# VOLTAGE_TOP.net
KiCad netlist of a schematic drawn in Altium Designer
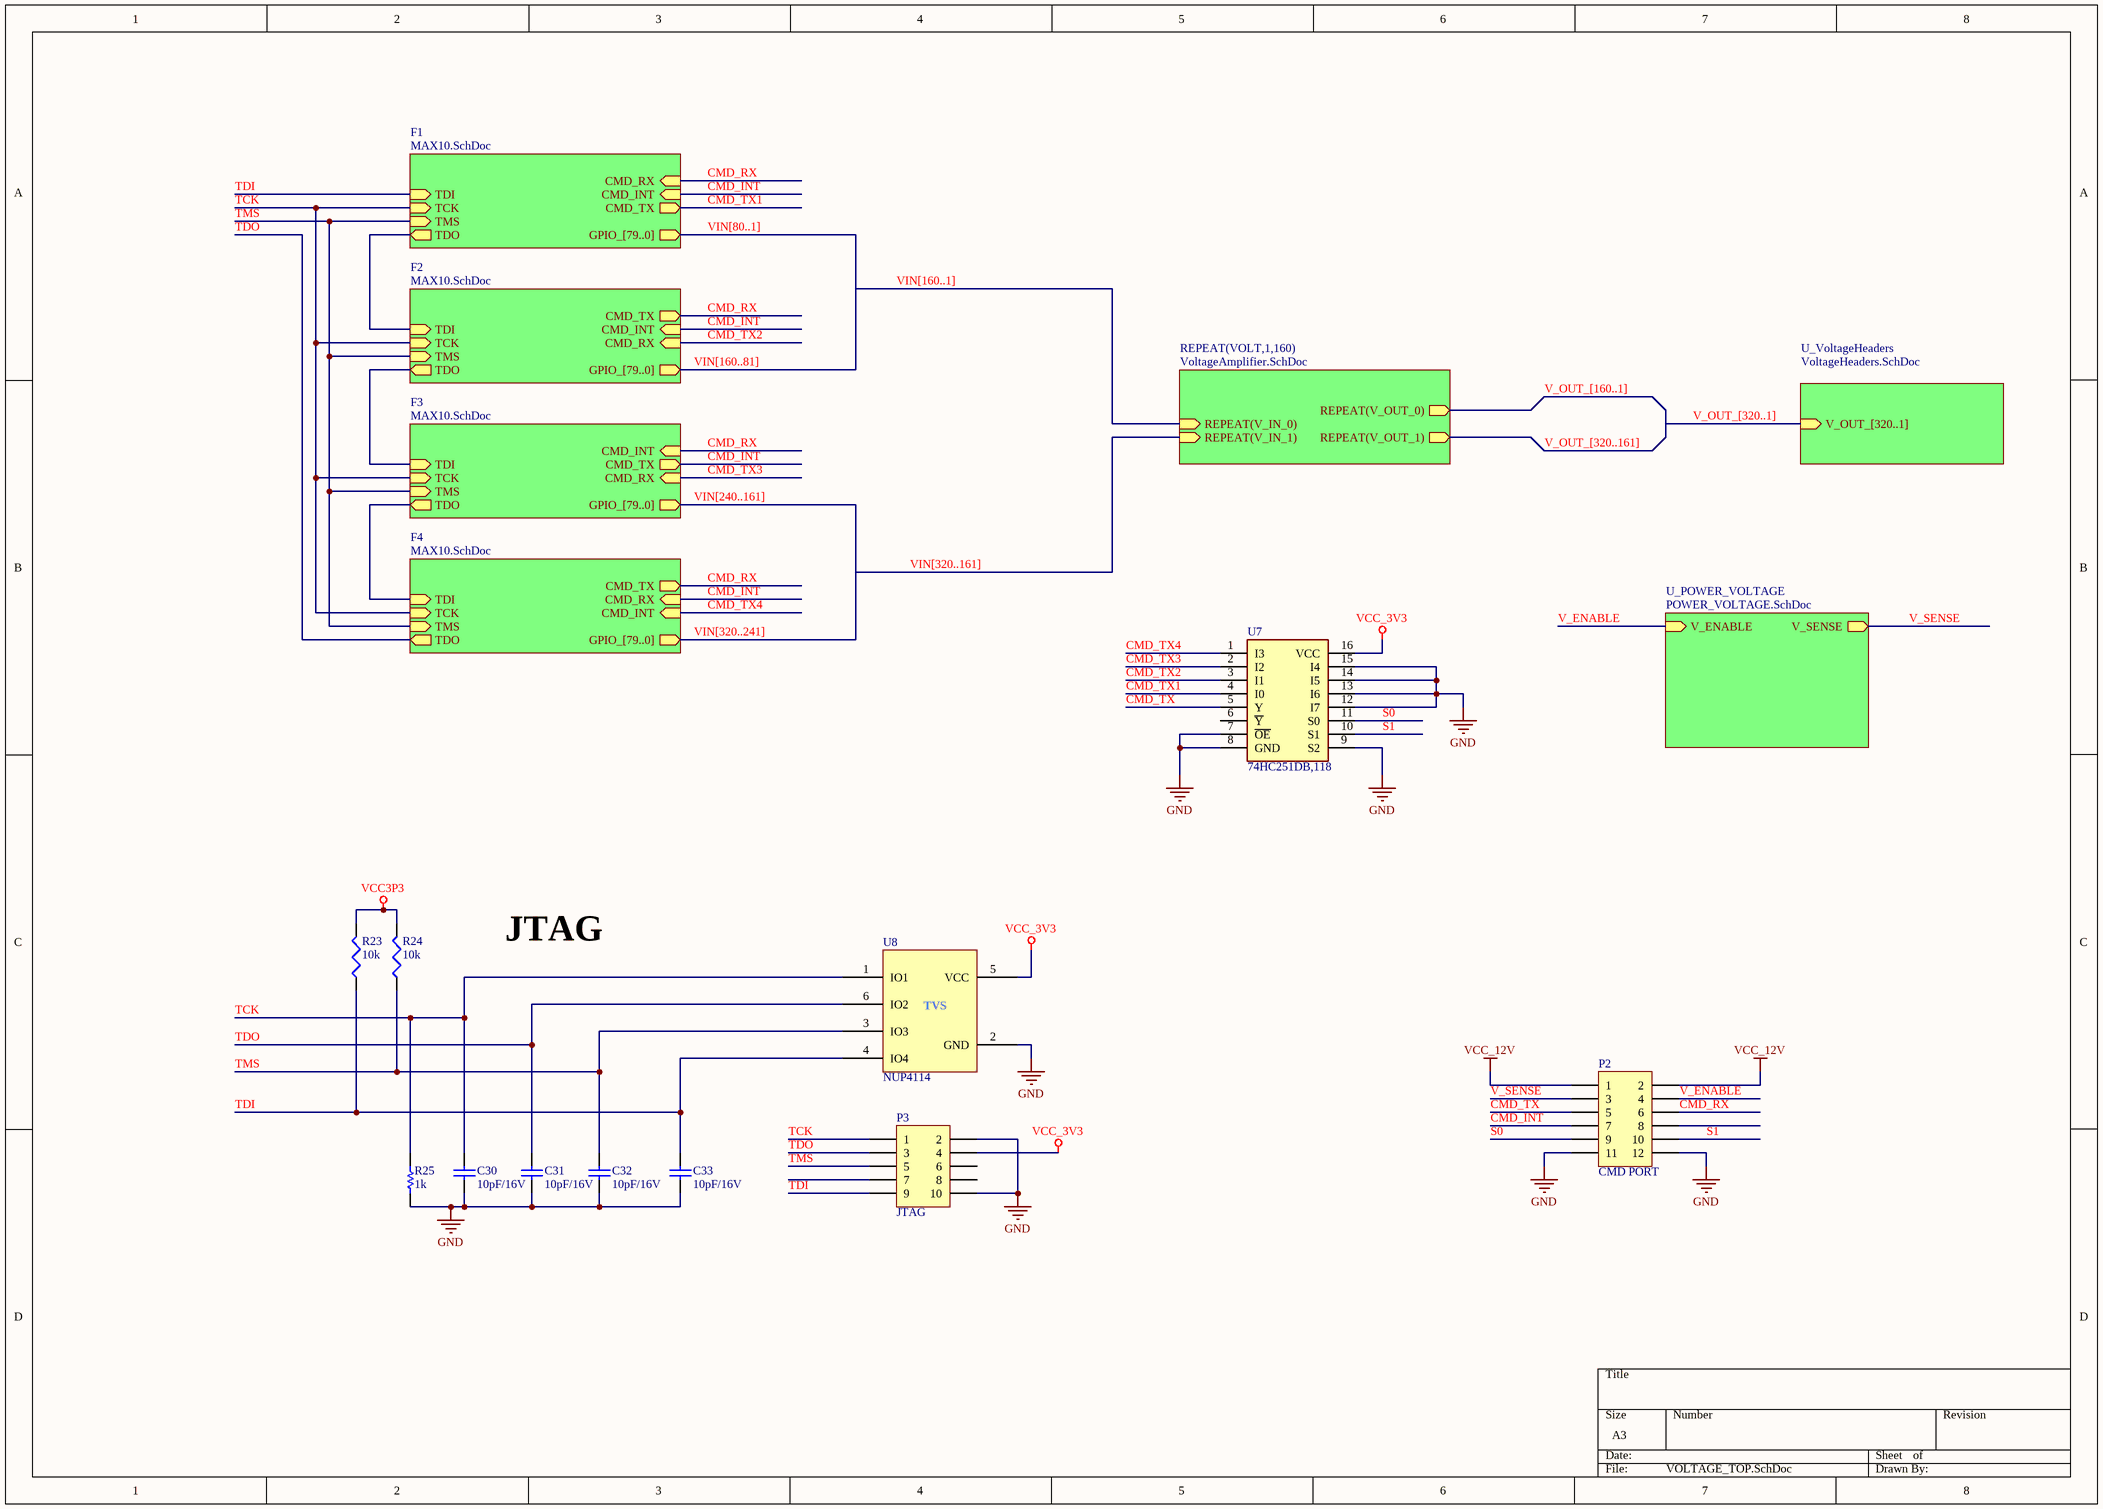
[diagram p0: VOLTAGE_TOP.SchDoc]

(export (version "E")
  (design (tool "Eeschema 10.0.6"))
  (components
    (comp (ref "C30")
      (value "10pF/16V")
      (footprint "0603_CAP")
      (description "Multilayer Ceramic Capacitors MLCC - SMD/SMT 16V 10pF 0603 X7R 0.1")
      (fields
        (field (name "STOCKIEST PART NO") "80-C0603C100K4RACTU")
        (field (name "MFR PART NO") "C0603C100K4RACTU")
      )
      (libsource (lib "Miscellaneous Devices") (part "Cap"))
    )
    (comp (ref "C31")
      (value "10pF/16V")
      (footprint "0603_CAP")
      (description "Multilayer Ceramic Capacitors MLCC - SMD/SMT 16V 10pF 0603 X7R 0.1")
      (fields
        (field (name "STOCKIEST PART NO") "80-C0603C100K4RACTU")
        (field (name "MFR PART NO") "C0603C100K4RACTU")
      )
      (libsource (lib "Miscellaneous Devices") (part "Cap"))
    )
    (comp (ref "C32")
      (value "10pF/16V")
      (footprint "0603_CAP")
      (description "Multilayer Ceramic Capacitors MLCC - SMD/SMT 16V 10pF 0603 X7R 0.1")
      (fields
        (field (name "STOCKIEST PART NO") "80-C0603C100K4RACTU")
        (field (name "MFR PART NO") "C0603C100K4RACTU")
      )
      (libsource (lib "Miscellaneous Devices") (part "Cap"))
    )
    (comp (ref "C33")
      (value "10pF/16V")
      (footprint "0603_CAP")
      (description "Multilayer Ceramic Capacitors MLCC - SMD/SMT 16V 10pF 0603 X7R 0.1")
      (fields
        (field (name "STOCKIEST PART NO") "80-C0603C100K4RACTU")
        (field (name "MFR PART NO") "C0603C100K4RACTU")
      )
      (libsource (lib "Miscellaneous Devices") (part "Cap"))
    )
    (comp (ref "P2")
      (value "CMD PORT")
      (footprint "HDR2X6")
      (description "Header, 6-Pin, Dual row")
      (fields (field (name "PUBLISHER") "Altium Limited"))
      (libsource (lib "Miscellaneous Connectors") (part "Header 6X2"))
    )
    (comp (ref "P3")
      (value "JTAG")
      (footprint "HDR2X5")
      (description "Header, 5-Pin, Dual row")
      (fields (field (name "PUBLISHER") "Altium Limited"))
      (libsource (lib "Miscellaneous Connectors") (part "Header 5X2"))
    )
    (comp (ref "R23")
      (value "10k")
      (footprint "0402_RES")
      (description "Thick Film Resistors - SMD 10K OHM 1%")
      (fields (field (name "MANUFACTURER") "Yageo") (field (name "STOCKIEST PART NO") "603-RC0402FR-0710KL"))
      (libsource (lib "altium-import") (part "root_1_0402_RES_"))
    )
    (comp (ref "R24")
      (value "10k")
      (footprint "0402_RES")
      (description "Thick Film Resistors - SMD 10K OHM 1%")
      (fields (field (name "MANUFACTURER") "Yageo") (field (name "STOCKIEST PART NO") "603-RC0402FR-0710KL"))
      (libsource (lib "altium-import") (part "root_1_0402_RES_"))
    )
    (comp (ref "R25")
      (value "1k")
      (footprint "RES_0805")
      (description "Thick Film Resistors - SMD 1/16W 1K Ohm 50V 1% ANTI SULFUR AEC-Q200")
      (fields
        (field (name "STOCKIEST PART NO") "603-AA0402FR-071KL")
        (field (name "MFR PART NO") "AA0402FR-071KL")
      )
      (libsource (lib "Miscellaneous Devices") (part "Res1"))
    )
    (comp (ref "U7")
      (value "74HC251DB,118")
      (footprint "SamacSys:SOP65P775X200-16N")
      (description "Integrated Circuit")
      (fields (field (name "MOUSER PART NUMBER") "771-HC251DB118"))
      (libsource (lib "*") (part "74HC251DB,118"))
    )
    (comp (ref "U8")
      (value "NUP4114")
      (footprint "NUP4114HMR6T1G")
      (description "ESD Suppressors / TVS Diodes LOW CAP TVS ARRAY 5.5V")
      (fields
        (field (name "MFR PART NO") "NUP4114HMR6T1G")
        (field (name "STOCKIEST PART NO") "863-NUP4114HMR6T1G")
      )
      (libsource (lib "Schlib1") (part "NUP4114"))
    )
  )
  (nets
    (net (code "401") (name "/CMD_INT") (class "Default")
      (node (ref "P2") (pin "7") (pinfunction "7_7") (pintype "passive"))
    )
    (net (code "402") (name "/CMD_RX") (class "Default")
      (node (ref "P2") (pin "6") (pinfunction "6_6") (pintype "passive"))
    )
    (net (code "403") (name "/CMD_TX") (class "Default")
      (node (ref "P2") (pin "5") (pinfunction "5_5") (pintype "passive"))
      (node (ref "U7") (pin "5") (pinfunction "Y_5") (pintype "passive"))
    )
    (net (code "404") (name "/CMD_TX1") (class "Default")
      (node (ref "U7") (pin "4") (pinfunction "I0_4") (pintype "passive"))
    )
    (net (code "405") (name "/CMD_TX2") (class "Default")
      (node (ref "U7") (pin "3") (pinfunction "I1_3") (pintype "passive"))
    )
    (net (code "406") (name "/CMD_TX3") (class "Default")
      (node (ref "U7") (pin "2") (pinfunction "I2_2") (pintype "passive"))
    )
    (net (code "407") (name "/CMD_TX4") (class "Default")
      (node (ref "U7") (pin "1") (pinfunction "I3_1") (pintype "passive"))
    )
    (net (code "410") (name "/S0") (class "Default")
      (node (ref "P2") (pin "9") (pinfunction "9_9") (pintype "passive"))
      (node (ref "U7") (pin "11") (pinfunction "S0_11") (pintype "passive"))
    )
    (net (code "411") (name "/S1") (class "Default")
      (node (ref "P2") (pin "10") (pinfunction "10_10") (pintype "passive"))
      (node (ref "U7") (pin "10") (pinfunction "S1_10") (pintype "passive"))
    )
    (net (code "412") (name "/TCK") (class "Default")
      (node (ref "C30") (pin "2") (pinfunction "2_2") (pintype "passive"))
      (node (ref "P3") (pin "1") (pinfunction "1_1") (pintype "passive"))
      (node (ref "R25") (pin "1") (pinfunction "1_1") (pintype "passive"))
      (node (ref "U8") (pin "1") (pinfunction "IO1_1") (pintype "passive"))
    )
    (net (code "413") (name "/TDI") (class "Default")
      (node (ref "C33") (pin "2") (pinfunction "2_2") (pintype "passive"))
      (node (ref "P3") (pin "9") (pinfunction "9_9") (pintype "passive"))
      (node (ref "R23") (pin "1") (pinfunction "1_1") (pintype "passive"))
      (node (ref "U8") (pin "4") (pinfunction "IO4_4") (pintype "passive"))
    )
    (net (code "414") (name "/TDO") (class "Default")
      (node (ref "C31") (pin "2") (pinfunction "2_2") (pintype "passive"))
      (node (ref "P3") (pin "3") (pinfunction "3_3") (pintype "passive"))
      (node (ref "U8") (pin "6") (pinfunction "IO2_6") (pintype "passive"))
    )
    (net (code "418") (name "/TMS") (class "Default")
      (node (ref "C32") (pin "2") (pinfunction "2_2") (pintype "passive"))
      (node (ref "P3") (pin "5") (pinfunction "5_5") (pintype "passive"))
      (node (ref "R24") (pin "1") (pinfunction "1_1") (pintype "passive"))
      (node (ref "U8") (pin "3") (pinfunction "IO3_3") (pintype "passive"))
    )
    (net (code "421") (name "/V_ENABLE") (class "Default")
      (node (ref "P2") (pin "4") (pinfunction "4_4") (pintype "passive"))
    )
    (net (code "423") (name "/V_SENSE") (class "Default")
      (node (ref "P2") (pin "3") (pinfunction "3_3") (pintype "passive"))
    )
    (net (code "424") (name "GND") (class "Default")
      (node (ref "C30") (pin "1") (pinfunction "1_1") (pintype "passive"))
      (node (ref "C31") (pin "1") (pinfunction "1_1") (pintype "passive"))
      (node (ref "C32") (pin "1") (pinfunction "1_1") (pintype "passive"))
      (node (ref "C33") (pin "1") (pinfunction "1_1") (pintype "passive"))
      (node (ref "P2") (pin "11") (pinfunction "11_11") (pintype "passive"))
      (node (ref "P2") (pin "12") (pinfunction "12_12") (pintype "passive"))
      (node (ref "P3") (pin "10") (pinfunction "10_10") (pintype "passive"))
      (node (ref "P3") (pin "2") (pinfunction "2_2") (pintype "passive"))
      (node (ref "R25") (pin "2") (pinfunction "2_2") (pintype "passive"))
      (node (ref "U7") (pin "12") (pinfunction "I7_12") (pintype "passive"))
      (node (ref "U7") (pin "13") (pinfunction "I6_13") (pintype "passive"))
      (node (ref "U7") (pin "14") (pinfunction "I5_14") (pintype "passive"))
      (node (ref "U7") (pin "15") (pinfunction "I4_15") (pintype "passive"))
      (node (ref "U7") (pin "7") (pinfunction "~{OE}_7") (pintype "passive"))
      (node (ref "U7") (pin "8") (pinfunction "GND_8") (pintype "passive"))
      (node (ref "U7") (pin "9") (pinfunction "S2_9") (pintype "passive"))
      (node (ref "U8") (pin "2") (pinfunction "GND_2") (pintype "passive"))
    )
    (net (code "425") (name "VCC3P3") (class "Default")
      (node (ref "R23") (pin "2") (pinfunction "2_2") (pintype "passive"))
      (node (ref "R24") (pin "2") (pinfunction "2_2") (pintype "passive"))
    )
    (net (code "426") (name "VCC_3V3") (class "Default")
      (node (ref "P3") (pin "4") (pinfunction "4_4") (pintype "passive"))
      (node (ref "U7") (pin "16") (pinfunction "VCC_16") (pintype "passive"))
      (node (ref "U8") (pin "5") (pinfunction "VCC_5") (pintype "passive"))
    )
    (net (code "427") (name "VCC_12V") (class "Default")
      (node (ref "P2") (pin "1") (pinfunction "1_1") (pintype "passive"))
      (node (ref "P2") (pin "2") (pinfunction "2_2") (pintype "passive"))
    )
    (net (code "428") (name "unconnected-(P2-Pad8)") (class "Default")
      (node (ref "P2") (pin "8") (pinfunction "8_8") (pintype "passive"))
    )
    (net (code "429") (name "unconnected-(P3-Pad6)") (class "Default")
      (node (ref "P3") (pin "6") (pinfunction "6_6") (pintype "passive"))
    )
    (net (code "430") (name "unconnected-(P3-Pad7)") (class "Default")
      (node (ref "P3") (pin "7") (pinfunction "7_7") (pintype "passive"))
    )
    (net (code "431") (name "unconnected-(P3-Pad8)") (class "Default")
      (node (ref "P3") (pin "8") (pinfunction "8_8") (pintype "passive"))
    )
    (net (code "432") (name "unconnected-(U7-~{Y}-Pad6)") (class "Default")
      (node (ref "U7") (pin "6") (pinfunction "~{Y}_6") (pintype "passive"))
    )
  )
)
